# hv_io_connector.net
KiCad netlist of a schematic drawn in Altium Designer
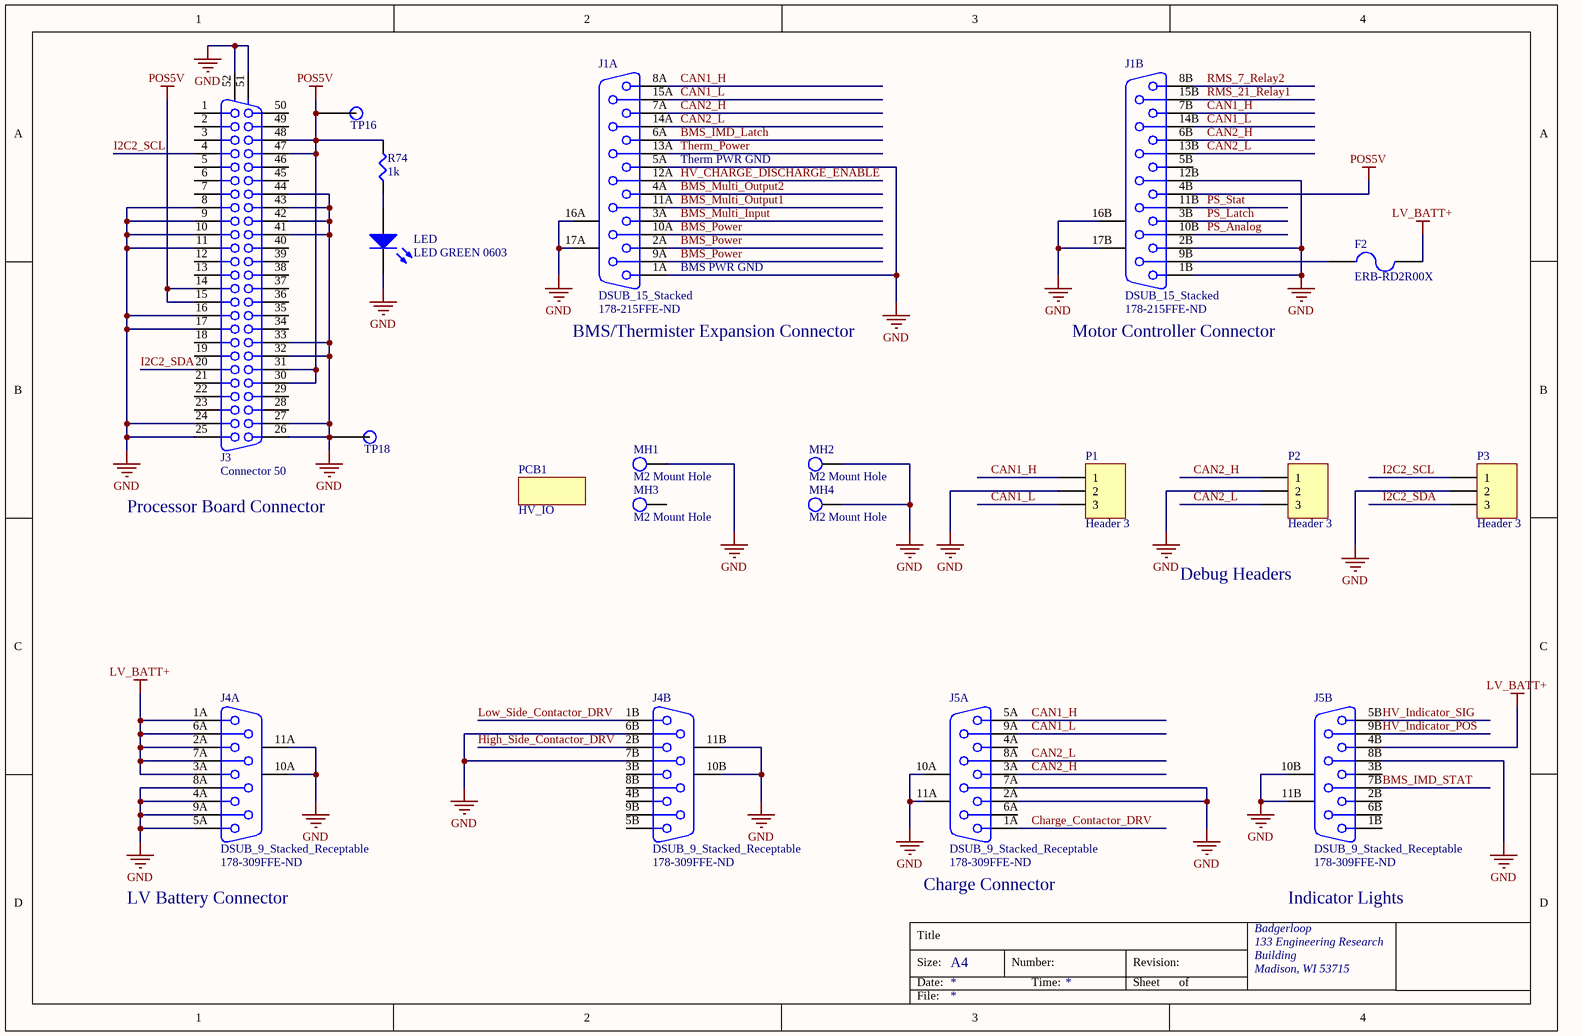
[diagram p0: hv_io_connector.SchDoc]

(export (version "E")
  (design (tool "Eeschema 10.0.6"))
  (components
    (comp (ref "F2")
      (value "ERB-RD2R00X")
      (footprint "SMD-0402-RES")
      (description "FUSE BOARD MOUNT 2A 32VDC 0402")
      (fields (field (name "MANUFACTURER") "Panasonic"))
      (libsource (lib "temp") (part "ERB-RD2R00X"))
    )
    (comp (ref "J1")
      (value "DSUB_15_Stacked")
      (footprint "DSUB_15_Stacked")
      (description "CONN D-SUB RCPT 15POS R/A SLDR")
      (fields
        (field (name "MANUFACTURER") "NorComp")
        (field (name "MANUFACTURER PART NUMBER") "178-015-513R491")
        (field (name "SUPPLIER PART NUMBER 1") "178-215FFE-ND")
      )
      (libsource (lib "temp") (part "DSUB_15_Stacked"))
    )
    (comp (ref "J3")
      (value "Connector 50")
      (footprint "050DSUB1.27-H96")
      (description "Plug Header Assembly")
      (fields (field (name "MANUFACTURER") "HARTING"))
      (libsource (lib "shelby_temp") (part "Connector 50"))
    )
    (comp (ref "J4")
      (value "DSUB_9_Stacked_Receptable")
      (footprint "DSUB_9_Stacked")
      (description "CONN D-SUB RCPT 9POS R/A SLDR")
      (fields
        (field (name "MANUFACTURER") "NorComp")
        (field (name "MANUFACTURER PART NUMBER") "178-009-513R691")
        (field (name "SUPPLIER PART NUMBER 1") "178-309FFE-ND")
      )
      (libsource (lib "temp") (part "DSUB_9_Stacked_Receptable"))
    )
    (comp (ref "J5")
      (value "DSUB_9_Stacked_Receptable")
      (footprint "DSUB_9_Stacked")
      (description "CONN D-SUB RCPT 9POS R/A SLDR")
      (fields
        (field (name "MANUFACTURER") "NorComp")
        (field (name "MANUFACTURER PART NUMBER") "178-009-513R691")
        (field (name "SUPPLIER PART NUMBER 1") "178-309FFE-ND")
      )
      (libsource (lib "temp") (part "DSUB_9_Stacked_Receptable"))
    )
    (comp (ref "LED")
      (value "LED GREEN 0603")
      (footprint "LED 0603 GREEN")
      (fields (field (name "MANUFACTURER") "Lite-On Inc."))
      (libsource (lib "altium-import") (part "root_3_LED GREEN 0603_"))
    )
    (comp (ref "MH1")
      (value "M2 Mount Hole")
      (footprint "MH")
      (libsource (lib "altium-import") (part "root_0_M2 Mount Hole_"))
    )
    (comp (ref "MH2")
      (value "M2 Mount Hole")
      (footprint "MH")
      (libsource (lib "altium-import") (part "root_0_M2 Mount Hole_"))
    )
    (comp (ref "MH3")
      (value "M2 Mount Hole")
      (footprint "MH")
      (libsource (lib "altium-import") (part "root_0_M2 Mount Hole_"))
    )
    (comp (ref "MH4")
      (value "M2 Mount Hole")
      (footprint "MH")
      (libsource (lib "altium-import") (part "root_0_M2 Mount Hole_"))
    )
    (comp (ref "P1")
      (value "Header 3")
      (footprint "Pin Header 1x3 TH Pitch 2.54mm")
      (description "Header, 3-Pin")
      (fields (field (name "PUBLISHER") "Altium Limited"))
      (libsource (lib "altium-import") (part "root_0_Header 3_"))
    )
    (comp (ref "P2")
      (value "Header 3")
      (footprint "Pin Header 1x3 TH Pitch 2.54mm")
      (description "Header, 3-Pin")
      (fields (field (name "PUBLISHER") "Altium Limited"))
      (libsource (lib "altium-import") (part "root_0_Header 3_"))
    )
    (comp (ref "P3")
      (value "Header 3")
      (footprint "Pin Header 1x3 TH Pitch 2.54mm")
      (description "Header, 3-Pin")
      (fields (field (name "PUBLISHER") "Altium Limited"))
      (libsource (lib "altium-import") (part "root_0_Header 3_"))
    )
    (comp (ref "PCB1") (value "HV_IO") (footprint "PCB") (libsource (lib "temp") (part "PCB")))
    (comp (ref "R74")
      (value "1k")
      (footprint "SMD-0805-RES")
      (description "RES SMD 1K OHM 5% 1/2W 0805")
      (fields
        (field (name "PART NUMBER") "ERJ-P06J102V")
        (field (name "DIGI-KEY PART NUMBER") "P1.0KADCT-ND")
      )
      (libsource (lib "altium-import") (part "root_1_ERJ-P06J102V_"))
    )
    (comp (ref "TP16") (value "TP") (footprint "Test Point") (libsource (lib "misc") (part "TP")))
    (comp (ref "TP18") (value "TP") (footprint "Test Point") (libsource (lib "misc") (part "TP")))
  )
  (nets
    (net (code "1") (name "/BMS_IMD_Latch") (class "Default")
      (node (ref "J1") (pin "6A") (pinfunction "6_6A") (pintype "passive"))
    )
    (net (code "2") (name "/BMS_IMD_STAT") (class "Default")
      (node (ref "J5") (pin "7B") (pinfunction "7_7B") (pintype "passive"))
    )
    (net (code "3") (name "/BMS_Multi_Input") (class "Default")
      (node (ref "J1") (pin "3A") (pinfunction "3_3A") (pintype "passive"))
    )
    (net (code "4") (name "/BMS_Multi_Output1") (class "Default")
      (node (ref "J1") (pin "11A") (pinfunction "11_11A") (pintype "passive"))
    )
    (net (code "5") (name "/BMS_Multi_Output2") (class "Default")
      (node (ref "J1") (pin "4A") (pinfunction "4_4A") (pintype "passive"))
    )
    (net (code "6") (name "/BMS_Power") (class "Default")
      (node (ref "J1") (pin "10A") (pinfunction "10_10A") (pintype "passive"))
      (node (ref "J1") (pin "2A") (pinfunction "2_2A") (pintype "passive"))
      (node (ref "J1") (pin "9A") (pinfunction "9_9A") (pintype "passive"))
    )
    (net (code "7") (name "/CAN1_H") (class "Default")
      (node (ref "J1") (pin "7B") (pinfunction "7_7B") (pintype "passive"))
      (node (ref "J1") (pin "8A") (pinfunction "8_8A") (pintype "passive"))
      (node (ref "J5") (pin "5A") (pinfunction "5_5A") (pintype "passive"))
      (node (ref "P1") (pin "1") (pinfunction "1_1") (pintype "passive"))
    )
    (net (code "8") (name "/CAN1_L") (class "Default")
      (node (ref "J1") (pin "14B") (pinfunction "14_14B") (pintype "passive"))
      (node (ref "J1") (pin "15A") (pinfunction "15_15A") (pintype "passive"))
      (node (ref "J5") (pin "9A") (pinfunction "9_9A") (pintype "passive"))
      (node (ref "P1") (pin "3") (pinfunction "3_3") (pintype "passive"))
    )
    (net (code "9") (name "/CAN2_H") (class "Default")
      (node (ref "J1") (pin "6B") (pinfunction "6_6B") (pintype "passive"))
      (node (ref "J1") (pin "7A") (pinfunction "7_7A") (pintype "passive"))
      (node (ref "J5") (pin "3A") (pinfunction "3_3A") (pintype "passive"))
      (node (ref "P2") (pin "1") (pinfunction "1_1") (pintype "passive"))
    )
    (net (code "10") (name "/CAN2_L") (class "Default")
      (node (ref "J1") (pin "13B") (pinfunction "13_13B") (pintype "passive"))
      (node (ref "J1") (pin "14A") (pinfunction "14_14A") (pintype "passive"))
      (node (ref "J5") (pin "8A") (pinfunction "8_8A") (pintype "passive"))
      (node (ref "P2") (pin "3") (pinfunction "3_3") (pintype "passive"))
    )
    (net (code "11") (name "/Charge_Contactor_DRV") (class "Default")
      (node (ref "J5") (pin "1A") (pinfunction "1_1A") (pintype "passive"))
    )
    (net (code "12") (name "/HV_CHARGE_DISCHARGE_ENABLE") (class "Default")
      (node (ref "J1") (pin "12A") (pinfunction "12_12A") (pintype "passive"))
    )
    (net (code "13") (name "/HV_Indicator_POS") (class "Default")
      (node (ref "J5") (pin "9B") (pinfunction "9_9B") (pintype "passive"))
    )
    (net (code "14") (name "/HV_Indicator_SIG") (class "Default")
      (node (ref "J5") (pin "5B") (pinfunction "5_5B") (pintype "passive"))
    )
    (net (code "15") (name "/High_Side_Contactor_DRV") (class "Default")
      (node (ref "J4") (pin "2B") (pinfunction "2_2B") (pintype "passive"))
    )
    (net (code "16") (name "/I2C2_SCL") (class "Default")
      (node (ref "J3") (pin "4") (pinfunction "4_4") (pintype "passive"))
      (node (ref "P3") (pin "1") (pinfunction "1_1") (pintype "passive"))
    )
    (net (code "17") (name "/I2C2_SDA") (class "Default")
      (node (ref "J3") (pin "20") (pinfunction "20_20") (pintype "passive"))
      (node (ref "P3") (pin "3") (pinfunction "3_3") (pintype "passive"))
    )
    (net (code "18") (name "/Low_Side_Contactor_DRV") (class "Default")
      (node (ref "J4") (pin "1B") (pinfunction "1_1B") (pintype "passive"))
    )
    (net (code "19") (name "/PS_Analog") (class "Default")
      (node (ref "J1") (pin "10B") (pinfunction "10_10B") (pintype "passive"))
    )
    (net (code "20") (name "/PS_Latch") (class "Default")
      (node (ref "J1") (pin "3B") (pinfunction "3_3B") (pintype "passive"))
    )
    (net (code "21") (name "/PS_Stat") (class "Default")
      (node (ref "J1") (pin "11B") (pinfunction "11_11B") (pintype "passive"))
    )
    (net (code "22") (name "/RMS_7_Relay2") (class "Default")
      (node (ref "J1") (pin "8B") (pinfunction "8_8B") (pintype "passive"))
    )
    (net (code "23") (name "/RMS_21_Relay1") (class "Default")
      (node (ref "J1") (pin "15B") (pinfunction "15_15B") (pintype "passive"))
    )
    (net (code "24") (name "/Therm_Power") (class "Default")
      (node (ref "J1") (pin "13A") (pinfunction "13_13A") (pintype "passive"))
    )
    (net (code "25") (name "GND") (class "Default")
      (node (ref "J1") (pin "12B") (pinfunction "12_12B") (pintype "passive"))
      (node (ref "J1") (pin "16A") (pinfunction "MH1_16A") (pintype "passive"))
      (node (ref "J1") (pin "16B") (pinfunction "MH1_16B") (pintype "passive"))
      (node (ref "J1") (pin "17A") (pinfunction "MH2_17A") (pintype "passive"))
      (node (ref "J1") (pin "17B") (pinfunction "MH2_17B") (pintype "passive"))
      (node (ref "J1") (pin "1A") (pinfunction "1_1A") (pintype "passive"))
      (node (ref "J1") (pin "1B") (pinfunction "1_1B") (pintype "passive"))
      (node (ref "J1") (pin "2B") (pinfunction "2_2B") (pintype "passive"))
      (node (ref "J1") (pin "5A") (pinfunction "5_5A") (pintype "passive"))
      (node (ref "J3") (pin "10") (pinfunction "10_10") (pintype "passive"))
      (node (ref "J3") (pin "11") (pinfunction "11_11") (pintype "passive"))
      (node (ref "J3") (pin "16") (pinfunction "16_16") (pintype "passive"))
      (node (ref "J3") (pin "17") (pinfunction "17_17") (pintype "passive"))
      (node (ref "J3") (pin "24") (pinfunction "24_24") (pintype "passive"))
      (node (ref "J3") (pin "25") (pinfunction "25_25") (pintype "passive"))
      (node (ref "J3") (pin "26") (pinfunction "26_26") (pintype "passive"))
      (node (ref "J3") (pin "27") (pinfunction "27_27") (pintype "passive"))
      (node (ref "J3") (pin "32") (pinfunction "32_32") (pintype "passive"))
      (node (ref "J3") (pin "33") (pinfunction "33_33") (pintype "passive"))
      (node (ref "J3") (pin "41") (pinfunction "41_41") (pintype "passive"))
      (node (ref "J3") (pin "42") (pinfunction "42_42") (pintype "passive"))
      (node (ref "J3") (pin "43") (pinfunction "43_43") (pintype "passive"))
      (node (ref "J3") (pin "44") (pinfunction "44_44") (pintype "passive"))
      (node (ref "J3") (pin "51") (pinfunction "51_51") (pintype "passive"))
      (node (ref "J3") (pin "52") (pinfunction "52_52") (pintype "passive"))
      (node (ref "J3") (pin "8") (pinfunction "8_8") (pintype "passive"))
      (node (ref "J3") (pin "9") (pinfunction "9_9") (pintype "passive"))
      (node (ref "J4") (pin "10A") (pinfunction "MH1_10A") (pintype "passive"))
      (node (ref "J4") (pin "10B") (pinfunction "MH1_10B") (pintype "passive"))
      (node (ref "J4") (pin "11A") (pinfunction "MH2_11A") (pintype "passive"))
      (node (ref "J4") (pin "11B") (pinfunction "MH2_11B") (pintype "passive"))
      (node (ref "J4") (pin "4A") (pinfunction "4_4A") (pintype "passive"))
      (node (ref "J4") (pin "5A") (pinfunction "5_5A") (pintype "passive"))
      (node (ref "J4") (pin "6B") (pinfunction "6_6B") (pintype "passive"))
      (node (ref "J4") (pin "7B") (pinfunction "7_7B") (pintype "passive"))
      (node (ref "J4") (pin "8A") (pinfunction "8_8A") (pintype "passive"))
      (node (ref "J4") (pin "9A") (pinfunction "9_9A") (pintype "passive"))
      (node (ref "J5") (pin "10A") (pinfunction "MH1_10A") (pintype "passive"))
      (node (ref "J5") (pin "10B") (pinfunction "MH1_10B") (pintype "passive"))
      (node (ref "J5") (pin "11A") (pinfunction "MH2_11A") (pintype "passive"))
      (node (ref "J5") (pin "11B") (pinfunction "MH2_11B") (pintype "passive"))
      (node (ref "J5") (pin "2A") (pinfunction "2_2A") (pintype "passive"))
      (node (ref "J5") (pin "7A") (pinfunction "7_7A") (pintype "passive"))
      (node (ref "J5") (pin "8B") (pinfunction "8_8B") (pintype "passive"))
      (node (ref "LED") (pin "2") (pinfunction "K_2") (pintype "passive"))
      (node (ref "MH1") (pin "1") (pinfunction "1_1") (pintype "passive"))
      (node (ref "MH2") (pin "1") (pinfunction "1_1") (pintype "passive"))
      (node (ref "MH4") (pin "1") (pinfunction "1_1") (pintype "passive"))
      (node (ref "P1") (pin "2") (pinfunction "2_2") (pintype "passive"))
      (node (ref "P2") (pin "2") (pinfunction "2_2") (pintype "passive"))
      (node (ref "P3") (pin "2") (pinfunction "2_2") (pintype "passive"))
      (node (ref "TP18") (pin "1") (pinfunction "1_1") (pintype "passive"))
    )
    (net (code "26") (name "LV_BATT+") (class "Default")
      (node (ref "F2") (pin "2") (pinfunction "2_2") (pintype "passive"))
      (node (ref "J4") (pin "1A") (pinfunction "1_1A") (pintype "passive"))
      (node (ref "J4") (pin "2A") (pinfunction "2_2A") (pintype "passive"))
      (node (ref "J4") (pin "3A") (pinfunction "3_3A") (pintype "passive"))
      (node (ref "J4") (pin "6A") (pinfunction "6_6A") (pintype "passive"))
      (node (ref "J4") (pin "7A") (pinfunction "7_7A") (pintype "passive"))
      (node (ref "J5") (pin "4B") (pinfunction "4_4B") (pintype "passive"))
    )
    (net (code "27") (name "Net-(J1B-9)") (class "Default")
      (node (ref "F2") (pin "1") (pinfunction "1_1") (pintype "passive"))
      (node (ref "J1") (pin "9B") (pinfunction "9_9B") (pintype "passive"))
    )
    (net (code "28") (name "Net-(LED-A)") (class "Default")
      (node (ref "LED") (pin "1") (pinfunction "A_1") (pintype "passive"))
      (node (ref "R74") (pin "1") (pinfunction "1_1") (pintype "passive"))
    )
    (net (code "29") (name "POS5V") (class "Default")
      (node (ref "J1") (pin "4B") (pinfunction "4_4B") (pintype "passive"))
      (node (ref "J3") (pin "14") (pinfunction "14_14") (pintype "passive"))
      (node (ref "J3") (pin "15") (pinfunction "15_15") (pintype "passive"))
      (node (ref "J3") (pin "30") (pinfunction "30_30") (pintype "passive"))
      (node (ref "J3") (pin "31") (pinfunction "31_31") (pintype "passive"))
      (node (ref "J3") (pin "47") (pinfunction "47_47") (pintype "passive"))
      (node (ref "J3") (pin "48") (pinfunction "48_48") (pintype "passive"))
      (node (ref "R74") (pin "2") (pinfunction "2_2") (pintype "passive"))
      (node (ref "TP16") (pin "1") (pinfunction "1_1") (pintype "passive"))
    )
    (net (code "30") (name "unconnected-(J1B-5-Pad5B)") (class "Default")
      (node (ref "J1") (pin "5B") (pinfunction "5_5B") (pintype "passive"))
    )
    (net (code "31") (name "unconnected-(J3-Pad1)") (class "Default")
      (node (ref "J3") (pin "1") (pinfunction "1_1") (pintype "passive"))
    )
    (net (code "32") (name "unconnected-(J3-Pad2)") (class "Default")
      (node (ref "J3") (pin "2") (pinfunction "2_2") (pintype "passive"))
    )
    (net (code "33") (name "unconnected-(J3-Pad3)") (class "Default")
      (node (ref "J3") (pin "3") (pinfunction "3_3") (pintype "passive"))
    )
    (net (code "34") (name "unconnected-(J3-Pad5)") (class "Default")
      (node (ref "J3") (pin "5") (pinfunction "5_5") (pintype "passive"))
    )
    (net (code "35") (name "unconnected-(J3-Pad6)") (class "Default")
      (node (ref "J3") (pin "6") (pinfunction "6_6") (pintype "passive"))
    )
    (net (code "36") (name "unconnected-(J3-Pad7)") (class "Default")
      (node (ref "J3") (pin "7") (pinfunction "7_7") (pintype "passive"))
    )
    (net (code "37") (name "unconnected-(J3-Pad12)") (class "Default")
      (node (ref "J3") (pin "12") (pinfunction "12_12") (pintype "passive"))
    )
    (net (code "38") (name "unconnected-(J3-Pad13)") (class "Default")
      (node (ref "J3") (pin "13") (pinfunction "13_13") (pintype "passive"))
    )
    (net (code "39") (name "unconnected-(J3-Pad18)") (class "Default")
      (node (ref "J3") (pin "18") (pinfunction "18_18") (pintype "passive"))
    )
    (net (code "40") (name "unconnected-(J3-Pad19)") (class "Default")
      (node (ref "J3") (pin "19") (pinfunction "19_19") (pintype "passive"))
    )
    (net (code "41") (name "unconnected-(J3-Pad21)") (class "Default")
      (node (ref "J3") (pin "21") (pinfunction "21_21") (pintype "passive"))
    )
    (net (code "42") (name "unconnected-(J3-Pad22)") (class "Default")
      (node (ref "J3") (pin "22") (pinfunction "22_22") (pintype "passive"))
    )
    (net (code "43") (name "unconnected-(J3-Pad23)") (class "Default")
      (node (ref "J3") (pin "23") (pinfunction "23_23") (pintype "passive"))
    )
    (net (code "44") (name "unconnected-(J3-Pad28)") (class "Default")
      (node (ref "J3") (pin "28") (pinfunction "28_28") (pintype "passive"))
    )
    (net (code "45") (name "unconnected-(J3-Pad29)") (class "Default")
      (node (ref "J3") (pin "29") (pinfunction "29_29") (pintype "passive"))
    )
    (net (code "46") (name "unconnected-(J3-Pad34)") (class "Default")
      (node (ref "J3") (pin "34") (pinfunction "34_34") (pintype "passive"))
    )
    (net (code "47") (name "unconnected-(J3-Pad35)") (class "Default")
      (node (ref "J3") (pin "35") (pinfunction "35_35") (pintype "passive"))
    )
    (net (code "48") (name "unconnected-(J3-Pad36)") (class "Default")
      (node (ref "J3") (pin "36") (pinfunction "36_36") (pintype "passive"))
    )
    (net (code "49") (name "unconnected-(J3-Pad37)") (class "Default")
      (node (ref "J3") (pin "37") (pinfunction "37_37") (pintype "passive"))
    )
    (net (code "50") (name "unconnected-(J3-Pad38)") (class "Default")
      (node (ref "J3") (pin "38") (pinfunction "38_38") (pintype "passive"))
    )
    (net (code "51") (name "unconnected-(J3-Pad39)") (class "Default")
      (node (ref "J3") (pin "39") (pinfunction "39_39") (pintype "passive"))
    )
    (net (code "52") (name "unconnected-(J3-Pad40)") (class "Default")
      (node (ref "J3") (pin "40") (pinfunction "40_40") (pintype "passive"))
    )
    (net (code "53") (name "unconnected-(J3-Pad45)") (class "Default")
      (node (ref "J3") (pin "45") (pinfunction "45_45") (pintype "passive"))
    )
    (net (code "54") (name "unconnected-(J3-Pad46)") (class "Default")
      (node (ref "J3") (pin "46") (pinfunction "46_46") (pintype "passive"))
    )
    (net (code "55") (name "unconnected-(J3-Pad49)") (class "Default")
      (node (ref "J3") (pin "49") (pinfunction "49_49") (pintype "passive"))
    )
    (net (code "56") (name "unconnected-(J3-Pad50)") (class "Default")
      (node (ref "J3") (pin "50") (pinfunction "50_50") (pintype "passive"))
    )
    (net (code "57") (name "unconnected-(J4B-3-Pad3B)") (class "Default")
      (node (ref "J4") (pin "3B") (pinfunction "3_3B") (pintype "passive"))
    )
    (net (code "58") (name "unconnected-(J4B-4-Pad4B)") (class "Default")
      (node (ref "J4") (pin "4B") (pinfunction "4_4B") (pintype "passive"))
    )
    (net (code "59") (name "unconnected-(J4B-5-Pad5B)") (class "Default")
      (node (ref "J4") (pin "5B") (pinfunction "5_5B") (pintype "passive"))
    )
    (net (code "60") (name "unconnected-(J4B-8-Pad8B)") (class "Default")
      (node (ref "J4") (pin "8B") (pinfunction "8_8B") (pintype "passive"))
    )
    (net (code "61") (name "unconnected-(J4B-9-Pad9B)") (class "Default")
      (node (ref "J4") (pin "9B") (pinfunction "9_9B") (pintype "passive"))
    )
    (net (code "62") (name "unconnected-(J5A-4-Pad4A)") (class "Default")
      (node (ref "J5") (pin "4A") (pinfunction "4_4A") (pintype "passive"))
    )
    (net (code "63") (name "unconnected-(J5A-6-Pad6A)") (class "Default")
      (node (ref "J5") (pin "6A") (pinfunction "6_6A") (pintype "passive"))
    )
    (net (code "64") (name "unconnected-(J5B-1-Pad1B)") (class "Default")
      (node (ref "J5") (pin "1B") (pinfunction "1_1B") (pintype "passive"))
    )
    (net (code "65") (name "unconnected-(J5B-2-Pad2B)") (class "Default")
      (node (ref "J5") (pin "2B") (pinfunction "2_2B") (pintype "passive"))
    )
    (net (code "66") (name "unconnected-(J5B-3-Pad3B)") (class "Default")
      (node (ref "J5") (pin "3B") (pinfunction "3_3B") (pintype "passive"))
    )
    (net (code "67") (name "unconnected-(J5B-6-Pad6B)") (class "Default")
      (node (ref "J5") (pin "6B") (pinfunction "6_6B") (pintype "passive"))
    )
    (net (code "68") (name "unconnected-(MH3-Pad1)") (class "Default")
      (node (ref "MH3") (pin "1") (pinfunction "1_1") (pintype "passive"))
    )
  )
)
